# xv11_board.net
KiCad netlist of a schematic drawn in Altium Designer
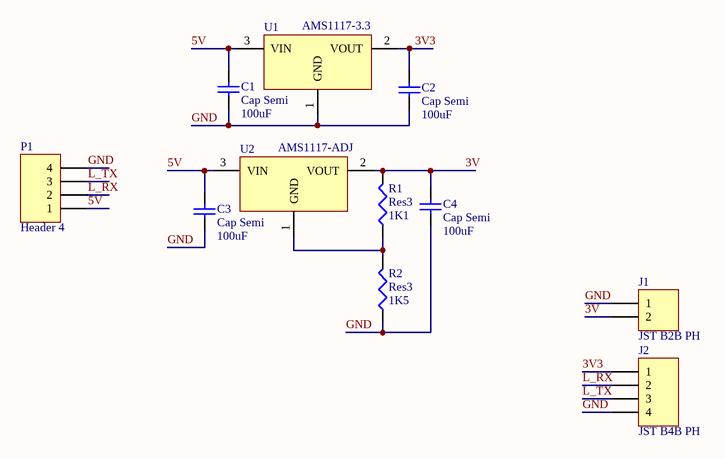
[diagram p0: xv11_board.SchDoc]

(export (version "E")
  (design (tool "Eeschema 10.0.6"))
  (components
    (comp (ref "C1")
      (value "Cap Semi")
      (footprint "C1206")
      (description "Capacitor (Semiconductor SIM Model)")
      (fields (field (name "ALTIUM_VALUE") "100uF") (field (name "PUBLISHER") "Altium Limited"))
      (libsource (lib "Miscellaneous Devices") (part "Cap Semi"))
    )
    (comp (ref "C2")
      (value "Cap Semi")
      (footprint "C1206")
      (description "Capacitor (Semiconductor SIM Model)")
      (fields (field (name "ALTIUM_VALUE") "100uF") (field (name "PUBLISHER") "Altium Limited"))
      (libsource (lib "Miscellaneous Devices") (part "Cap Semi"))
    )
    (comp (ref "C3")
      (value "Cap Semi")
      (footprint "C1206")
      (description "Capacitor (Semiconductor SIM Model)")
      (fields (field (name "ALTIUM_VALUE") "100uF") (field (name "PUBLISHER") "Altium Limited"))
      (libsource (lib "Miscellaneous Devices") (part "Cap Semi"))
    )
    (comp (ref "C4")
      (value "Cap Semi")
      (footprint "C1206")
      (description "Capacitor (Semiconductor SIM Model)")
      (fields (field (name "ALTIUM_VALUE") "100uF") (field (name "PUBLISHER") "Altium Limited"))
      (libsource (lib "Miscellaneous Devices") (part "Cap Semi"))
    )
    (comp (ref "J1")
      (value "JST B2B PH")
      (footprint "JST B2B-PH-K")
      (description "JST PH Header, 2-Pin")
      (libsource (lib "MyLib") (part "JST B2B PH"))
    )
    (comp (ref "J2")
      (value "JST B4B PH")
      (footprint "JST B4B-PH-K")
      (description "JST PH Header, 4-Pin")
      (libsource (lib "MyLib") (part "JST B4B PH"))
    )
    (comp (ref "P1")
      (value "Header 4")
      (footprint "HDR1X4")
      (description "Header, 4-Pin")
      (fields (field (name "PUBLISHER") "Altium Limited"))
      (libsource (lib "Miscellaneous Connectors") (part "Header 4"))
    )
    (comp (ref "R1")
      (value "Res3")
      (footprint "J1-0603")
      (description "Resistor")
      (fields (field (name "ALTIUM_VALUE") "1K1") (field (name "PUBLISHER") "Altium Limited"))
      (libsource (lib "Miscellaneous Devices") (part "Res3"))
    )
    (comp (ref "R2")
      (value "Res3")
      (footprint "J1-0603")
      (description "Resistor")
      (fields (field (name "ALTIUM_VALUE") "1K5") (field (name "PUBLISHER") "Altium Limited"))
      (libsource (lib "Miscellaneous Devices") (part "Res3"))
    )
    (comp (ref "U1")
      (value "AMS1117-3.3")
      (footprint "SOT-223")
      (description "3.3V  3-Terminal Adjustable Positive Voltage Regulator")
      (libsource (lib "Analog IC") (part "AMS1117-3.3"))
    )
    (comp (ref "U2")
      (value "AMS1117-ADJ")
      (footprint "SOT-223")
      (description "3.3V  3-Terminal Adjustable Positive Voltage Regulator")
      (libsource (lib "Analog IC") (part "AMS1117-3.3"))
    )
  )
  (nets
    (net (code "1") (name "/3V") (class "Default")
      (node (ref "C4") (pin "2") (pinfunction "2_2") (pintype "passive"))
      (node (ref "J1") (pin "2") (pinfunction "2_2") (pintype "passive"))
      (node (ref "R1") (pin "2") (pinfunction "2_2") (pintype "passive"))
      (node (ref "U2") (pin "2") (pinfunction "VOUT_2") (pintype "passive"))
    )
    (net (code "2") (name "/3V3") (class "Default")
      (node (ref "C2") (pin "2") (pinfunction "2_2") (pintype "passive"))
      (node (ref "J2") (pin "1") (pinfunction "1_1") (pintype "passive"))
      (node (ref "U1") (pin "2") (pinfunction "VOUT_2") (pintype "passive"))
    )
    (net (code "3") (name "/5V") (class "Default")
      (node (ref "C1") (pin "2") (pinfunction "2_2") (pintype "passive"))
      (node (ref "C3") (pin "2") (pinfunction "2_2") (pintype "passive"))
      (node (ref "P1") (pin "1") (pinfunction "1_1") (pintype "passive"))
      (node (ref "U1") (pin "3") (pinfunction "VIN_3") (pintype "passive"))
      (node (ref "U2") (pin "3") (pinfunction "VIN_3") (pintype "passive"))
    )
    (net (code "4") (name "/GND") (class "Default")
      (node (ref "C1") (pin "1") (pinfunction "1_1") (pintype "passive"))
      (node (ref "C2") (pin "1") (pinfunction "1_1") (pintype "passive"))
      (node (ref "C3") (pin "1") (pinfunction "1_1") (pintype "passive"))
      (node (ref "C4") (pin "1") (pinfunction "1_1") (pintype "passive"))
      (node (ref "J1") (pin "1") (pinfunction "1_1") (pintype "passive"))
      (node (ref "J2") (pin "4") (pinfunction "4_4") (pintype "passive"))
      (node (ref "P1") (pin "4") (pinfunction "4_4") (pintype "passive"))
      (node (ref "R2") (pin "1") (pinfunction "1_1") (pintype "passive"))
      (node (ref "U1") (pin "1") (pinfunction "GND_1") (pintype "passive"))
    )
    (net (code "5") (name "/L_RX") (class "Default")
      (node (ref "J2") (pin "2") (pinfunction "2_2") (pintype "passive"))
      (node (ref "P1") (pin "2") (pinfunction "2_2") (pintype "passive"))
    )
    (net (code "6") (name "/L_TX") (class "Default")
      (node (ref "J2") (pin "3") (pinfunction "3_3") (pintype "passive"))
      (node (ref "P1") (pin "3") (pinfunction "3_3") (pintype "passive"))
    )
    (net (code "7") (name "Net-(U2-GND)") (class "Default")
      (node (ref "R1") (pin "1") (pinfunction "1_1") (pintype "passive"))
      (node (ref "R2") (pin "2") (pinfunction "2_2") (pintype "passive"))
      (node (ref "U2") (pin "1") (pinfunction "GND_1") (pintype "passive"))
    )
  )
)
